# NONCONTACT-THERMOMETER.net
KiCad netlist of a schematic drawn in Altium Designer
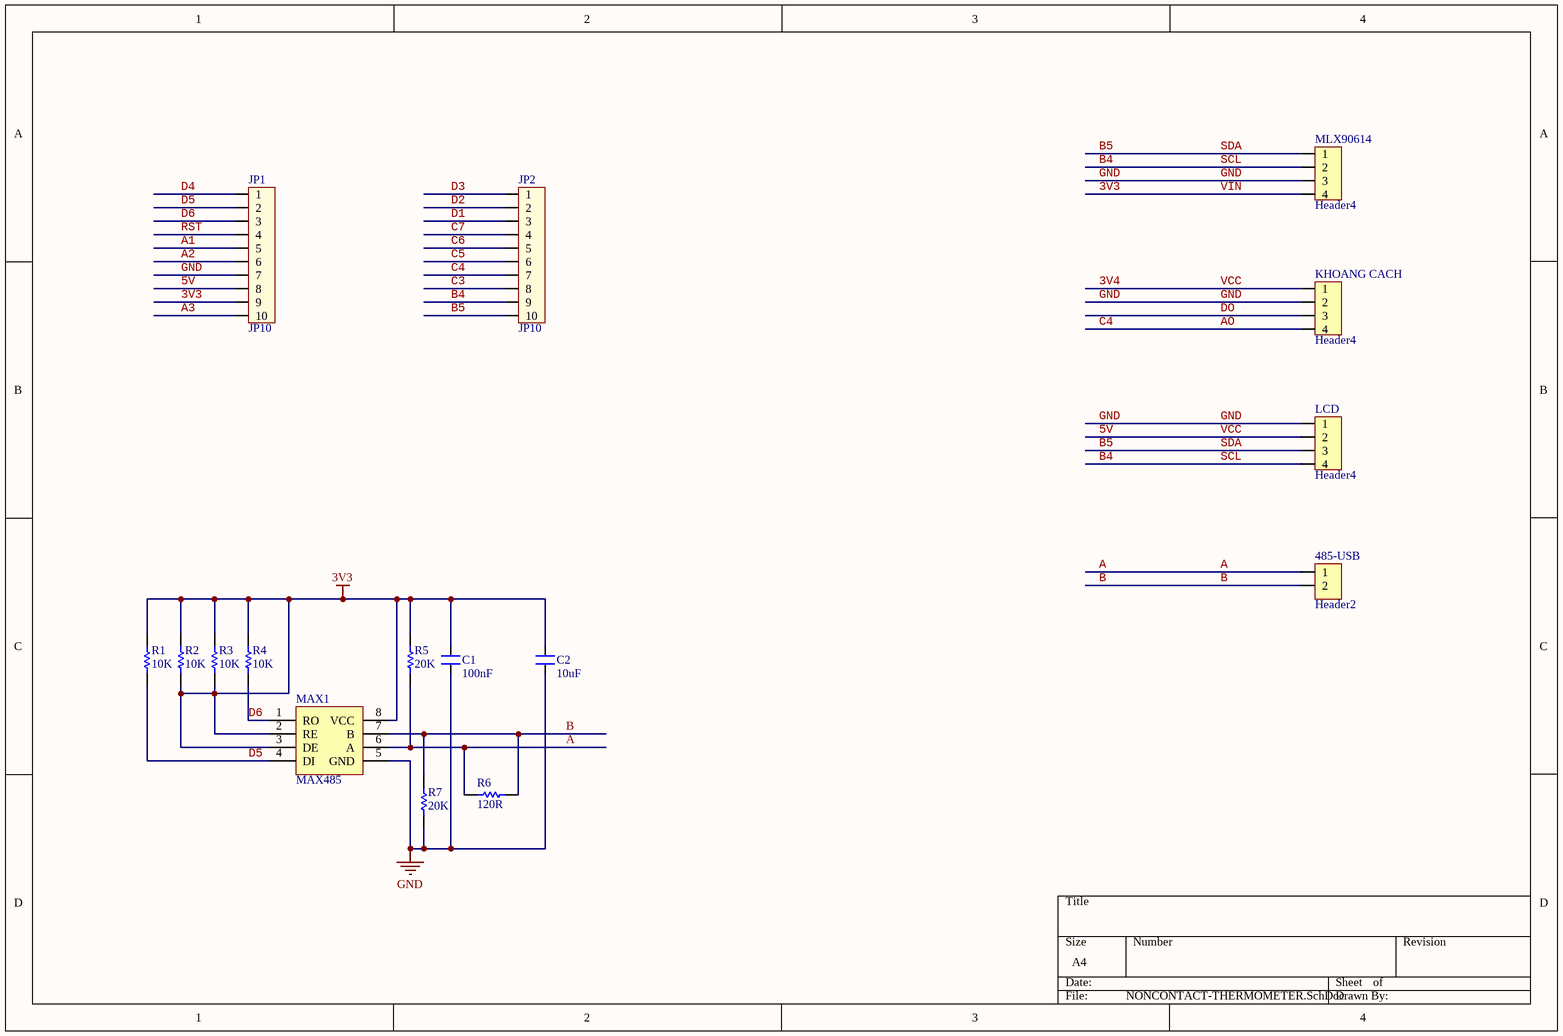
[diagram p0: NONCONTACT-THERMOMETER.SchDoc]

(export (version "E")
  (design (tool "Eeschema 10.0.6"))
  (components
    (comp (ref "485-USB")
      (value "Header2")
      (footprint "HDR2")
      (description "Header IDC, 2 x 1 Pin Vertical 2.54mm Pitch (Non-Boxed, Male)")
      (fields
        (field (name "MANUFACTURER") "Würth Elektronik eiSos GmbH")
        (field (name "PARTNO") "613002143121")
        (field (name "CREATED BY") "Karrer Zheng")
      )
      (libsource (lib "LIBRARY_MuaLinhKien") (part "Header2"))
    )
    (comp (ref "C1")
      (value "100nF")
      (footprint "CAP 0603(1508)")
      (description "Ceramic Capacitor 1nF/50V (+-20% TH)/(+10%SMD)")
      (libsource (lib "Duc") (part "CAP_CER_0.1uF_50V_NPOL_1"))
    )
    (comp (ref "C2")
      (value "10uF")
      (footprint "CAP 0603(1508)")
      (description "Ceramic Capacitor 1nF/50V (+-20% TH)/(+10%SMD)")
      (libsource (lib "Duc") (part "CAP_CER_0.1uF_50V_NPOL_1"))
    )
    (comp (ref "JP1")
      (value "JP10")
      (footprint "Header10")
      (description "Connector 10")
      (libsource (lib "LIBRARY_MuaLinhKien") (part "Header10"))
    )
    (comp (ref "JP2")
      (value "JP10")
      (footprint "Header10")
      (description "Connector 10")
      (libsource (lib "LIBRARY_MuaLinhKien") (part "Header10"))
    )
    (comp (ref "KHOANG CACH")
      (value "Header4")
      (footprint "HDR4")
      (description "Header IDC, 4 x 1 Pin Vertical 2.54mm Pitch (Non-Boxed, Male)")
      (fields
        (field (name "MANUFACTURER") "Würth Elektronik eiSos GmbH")
        (field (name "PARTNO") "613002143121")
        (field (name "CREATED BY") "Karrer Zheng")
      )
      (libsource (lib "LIBRARY_MuaLinhKien") (part "Header4"))
    )
    (comp (ref "LCD")
      (value "Header4")
      (footprint "HDR4")
      (description "Header IDC, 4 x 1 Pin Vertical 2.54mm Pitch (Non-Boxed, Male)")
      (fields
        (field (name "MANUFACTURER") "Würth Elektronik eiSos GmbH")
        (field (name "PARTNO") "613002143121")
        (field (name "CREATED BY") "Karrer Zheng")
      )
      (libsource (lib "LIBRARY_MuaLinhKien") (part "Header4"))
    )
    (comp (ref "MAX1")
      (value "MAX485")
      (footprint "MAX485")
      (description "MAX3485")
      (libsource (lib "Duc") (part "MAX485"))
    )
    (comp (ref "MLX90614")
      (value "Header4")
      (footprint "HDR4")
      (description "Header IDC, 4 x 1 Pin Vertical 2.54mm Pitch (Non-Boxed, Male)")
      (fields
        (field (name "MANUFACTURER") "Würth Elektronik eiSos GmbH")
        (field (name "PARTNO") "613002143121")
        (field (name "CREATED BY") "Karrer Zheng")
      )
      (libsource (lib "LIBRARY_MuaLinhKien") (part "Header4"))
    )
    (comp (ref "R1")
      (value "10K")
      (footprint "RES 0603(1608)")
      (description "Resistor 0603")
      (libsource (lib "Duc") (part "Resistor 0603"))
    )
    (comp (ref "R2")
      (value "10K")
      (footprint "RES 0603(1608)")
      (description "Resistor 0603")
      (libsource (lib "Duc") (part "Resistor 0603"))
    )
    (comp (ref "R3")
      (value "10K")
      (footprint "RES 0603(1608)")
      (description "Resistor 0603")
      (libsource (lib "Duc") (part "Resistor 0603"))
    )
    (comp (ref "R4")
      (value "10K")
      (footprint "RES 0603(1608)")
      (description "Resistor 0603")
      (libsource (lib "Duc") (part "Resistor 0603"))
    )
    (comp (ref "R5")
      (value "20K")
      (footprint "RES 0603(1608)")
      (description "Resistor 0603")
      (libsource (lib "Duc") (part "Resistor 0603"))
    )
    (comp (ref "R6")
      (value "120R")
      (footprint "RES 0603(1608)")
      (description "Resistor 0603")
      (libsource (lib "Duc") (part "Resistor 0603"))
    )
    (comp (ref "R7")
      (value "20K")
      (footprint "RES 0603(1608)")
      (description "Resistor 0603")
      (libsource (lib "Duc") (part "Resistor 0603"))
    )
  )
  (nets
    (net (code "1") (name "/3V4") (class "Default")
      (node (ref "JP1") (pin "8") (pinfunction "8_8") (pintype "passive"))
      (node (ref "KHOANG CACH") (pin "1") (pinfunction "1_1") (pintype "passive"))
      (node (ref "LCD") (pin "2") (pinfunction "2_2") (pintype "passive"))
    )
    (net (code "2") (name "/A") (class "Default")
      (node (ref "485-USB") (pin "1") (pinfunction "1_1") (pintype "passive"))
      (node (ref "MAX1") (pin "6") (pinfunction "A_6") (pintype "passive"))
      (node (ref "R5") (pin "2") (pinfunction "2_2") (pintype "passive"))
      (node (ref "R6") (pin "1") (pinfunction "1_1") (pintype "passive"))
    )
    (net (code "3") (name "/A1") (class "Default")
      (node (ref "JP1") (pin "5") (pinfunction "5_5") (pintype "passive"))
    )
    (net (code "4") (name "/A2") (class "Default")
      (node (ref "JP1") (pin "6") (pinfunction "6_6") (pintype "passive"))
    )
    (net (code "5") (name "/A3") (class "Default")
      (node (ref "JP1") (pin "10") (pinfunction "10_10") (pintype "passive"))
    )
    (net (code "6") (name "/AO") (class "Default")
      (node (ref "JP2") (pin "7") (pinfunction "7_7") (pintype "passive"))
      (node (ref "KHOANG CACH") (pin "4") (pinfunction "4_4") (pintype "passive"))
    )
    (net (code "7") (name "/B") (class "Default")
      (node (ref "485-USB") (pin "2") (pinfunction "2_2") (pintype "passive"))
      (node (ref "MAX1") (pin "7") (pinfunction "B_7") (pintype "passive"))
      (node (ref "R6") (pin "2") (pinfunction "2_2") (pintype "passive"))
      (node (ref "R7") (pin "1") (pinfunction "1_1") (pintype "passive"))
    )
    (net (code "8") (name "/B4") (class "Default")
      (node (ref "JP2") (pin "9") (pinfunction "9_9") (pintype "passive"))
      (node (ref "LCD") (pin "4") (pinfunction "4_4") (pintype "passive"))
      (node (ref "MLX90614") (pin "2") (pinfunction "2_2") (pintype "passive"))
    )
    (net (code "9") (name "/B5") (class "Default")
      (node (ref "JP2") (pin "10") (pinfunction "10_10") (pintype "passive"))
      (node (ref "LCD") (pin "3") (pinfunction "3_3") (pintype "passive"))
      (node (ref "MLX90614") (pin "1") (pinfunction "1_1") (pintype "passive"))
    )
    (net (code "10") (name "/C3") (class "Default")
      (node (ref "JP2") (pin "8") (pinfunction "8_8") (pintype "passive"))
    )
    (net (code "11") (name "/C5") (class "Default")
      (node (ref "JP2") (pin "6") (pinfunction "6_6") (pintype "passive"))
    )
    (net (code "12") (name "/C6") (class "Default")
      (node (ref "JP2") (pin "5") (pinfunction "5_5") (pintype "passive"))
    )
    (net (code "13") (name "/C7") (class "Default")
      (node (ref "JP2") (pin "4") (pinfunction "4_4") (pintype "passive"))
    )
    (net (code "14") (name "/D1") (class "Default")
      (node (ref "JP2") (pin "3") (pinfunction "3_3") (pintype "passive"))
    )
    (net (code "15") (name "/D2") (class "Default")
      (node (ref "JP2") (pin "2") (pinfunction "2_2") (pintype "passive"))
    )
    (net (code "16") (name "/D3") (class "Default")
      (node (ref "JP2") (pin "1") (pinfunction "1_1") (pintype "passive"))
    )
    (net (code "17") (name "/D4") (class "Default")
      (node (ref "JP1") (pin "1") (pinfunction "1_1") (pintype "passive"))
    )
    (net (code "18") (name "/D5") (class "Default")
      (node (ref "JP1") (pin "2") (pinfunction "2_2") (pintype "passive"))
      (node (ref "MAX1") (pin "4") (pinfunction "DI_4") (pintype "passive"))
      (node (ref "R1") (pin "2") (pinfunction "2_2") (pintype "passive"))
    )
    (net (code "19") (name "/D6") (class "Default")
      (node (ref "JP1") (pin "3") (pinfunction "3_3") (pintype "passive"))
      (node (ref "MAX1") (pin "1") (pinfunction "RO_1") (pintype "passive"))
      (node (ref "R4") (pin "2") (pinfunction "2_2") (pintype "passive"))
    )
    (net (code "20") (name "/DO") (class "Default")
      (node (ref "KHOANG CACH") (pin "3") (pinfunction "3_3") (pintype "passive"))
    )
    (net (code "21") (name "/RST") (class "Default")
      (node (ref "JP1") (pin "4") (pinfunction "4_4") (pintype "passive"))
    )
    (net (code "22") (name "3V3") (class "Default")
      (node (ref "C1") (pin "1") (pinfunction "1_1") (pintype "passive"))
      (node (ref "C2") (pin "1") (pinfunction "1_1") (pintype "passive"))
      (node (ref "JP1") (pin "9") (pinfunction "9_9") (pintype "passive"))
      (node (ref "MAX1") (pin "2") (pinfunction "RE_2") (pintype "passive"))
      (node (ref "MAX1") (pin "3") (pinfunction "DE_3") (pintype "passive"))
      (node (ref "MAX1") (pin "8") (pinfunction "VCC_8") (pintype "passive"))
      (node (ref "MLX90614") (pin "4") (pinfunction "4_4") (pintype "passive"))
      (node (ref "R1") (pin "1") (pinfunction "1_1") (pintype "passive"))
      (node (ref "R2") (pin "1") (pinfunction "1_1") (pintype "passive"))
      (node (ref "R2") (pin "2") (pinfunction "2_2") (pintype "passive"))
      (node (ref "R3") (pin "1") (pinfunction "1_1") (pintype "passive"))
      (node (ref "R3") (pin "2") (pinfunction "2_2") (pintype "passive"))
      (node (ref "R4") (pin "1") (pinfunction "1_1") (pintype "passive"))
      (node (ref "R5") (pin "1") (pinfunction "1_1") (pintype "passive"))
    )
    (net (code "23") (name "GND") (class "Default")
      (node (ref "C1") (pin "2") (pinfunction "2_2") (pintype "passive"))
      (node (ref "C2") (pin "2") (pinfunction "2_2") (pintype "passive"))
      (node (ref "JP1") (pin "7") (pinfunction "7_7") (pintype "passive"))
      (node (ref "KHOANG CACH") (pin "2") (pinfunction "2_2") (pintype "passive"))
      (node (ref "LCD") (pin "1") (pinfunction "1_1") (pintype "passive"))
      (node (ref "MAX1") (pin "5") (pinfunction "GND_5") (pintype "passive"))
      (node (ref "MLX90614") (pin "3") (pinfunction "3_3") (pintype "passive"))
      (node (ref "R7") (pin "2") (pinfunction "2_2") (pintype "passive"))
    )
  )
)
